# XT60.net
KiCad netlist of a schematic drawn in EAGLE
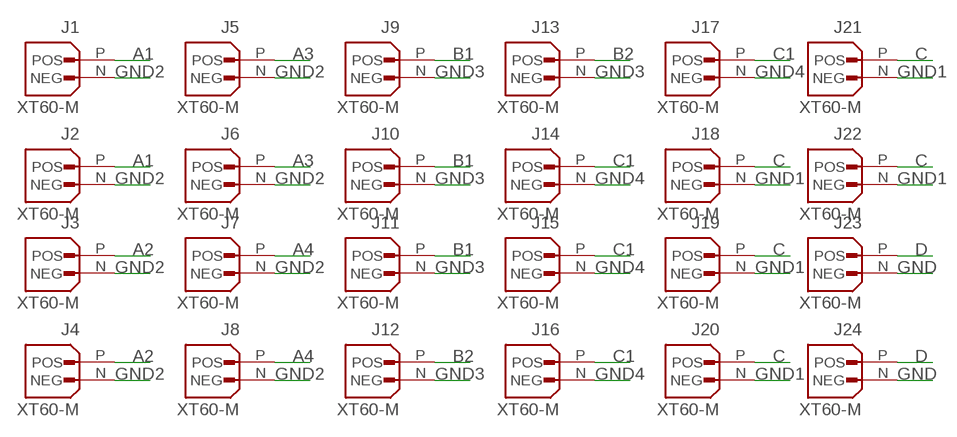
[diagram p0: schematic, sheet 1]

(export (version "E")
  (design (tool "Eeschema 10.0.6"))
  (components
    (comp (ref "J1")
      (value "XT60-M")
      (footprint "eagle-import:AMASS_XT60-M")
      (fields (field (name "MF") "AMASS"))
      (libsource (lib "eagle-import") (part "XT60-M"))
    )
    (comp (ref "J2")
      (value "XT60-M")
      (footprint "eagle-import:AMASS_XT60-M")
      (fields (field (name "MF") "AMASS"))
      (libsource (lib "eagle-import") (part "XT60-M"))
    )
    (comp (ref "J3")
      (value "XT60-M")
      (footprint "eagle-import:AMASS_XT60-M")
      (fields (field (name "MF") "AMASS"))
      (libsource (lib "eagle-import") (part "XT60-M"))
    )
    (comp (ref "J4")
      (value "XT60-M")
      (footprint "eagle-import:AMASS_XT60-M")
      (fields (field (name "MF") "AMASS"))
      (libsource (lib "eagle-import") (part "XT60-M"))
    )
    (comp (ref "J5")
      (value "XT60-M")
      (footprint "eagle-import:AMASS_XT60-M")
      (fields (field (name "MF") "AMASS"))
      (libsource (lib "eagle-import") (part "XT60-M"))
    )
    (comp (ref "J6")
      (value "XT60-M")
      (footprint "eagle-import:AMASS_XT60-M")
      (fields (field (name "MF") "AMASS"))
      (libsource (lib "eagle-import") (part "XT60-M"))
    )
    (comp (ref "J7")
      (value "XT60-M")
      (footprint "eagle-import:AMASS_XT60-M")
      (fields (field (name "MF") "AMASS"))
      (libsource (lib "eagle-import") (part "XT60-M"))
    )
    (comp (ref "J8")
      (value "XT60-M")
      (footprint "eagle-import:AMASS_XT60-M")
      (fields (field (name "MF") "AMASS"))
      (libsource (lib "eagle-import") (part "XT60-M"))
    )
    (comp (ref "J9")
      (value "XT60-M")
      (footprint "eagle-import:AMASS_XT60-M")
      (fields (field (name "MF") "AMASS"))
      (libsource (lib "eagle-import") (part "XT60-M"))
    )
    (comp (ref "J10")
      (value "XT60-M")
      (footprint "eagle-import:AMASS_XT60-M")
      (fields (field (name "MF") "AMASS"))
      (libsource (lib "eagle-import") (part "XT60-M"))
    )
    (comp (ref "J11")
      (value "XT60-M")
      (footprint "eagle-import:AMASS_XT60-M")
      (fields (field (name "MF") "AMASS"))
      (libsource (lib "eagle-import") (part "XT60-M"))
    )
    (comp (ref "J12")
      (value "XT60-M")
      (footprint "eagle-import:AMASS_XT60-M")
      (fields (field (name "MF") "AMASS"))
      (libsource (lib "eagle-import") (part "XT60-M"))
    )
    (comp (ref "J13")
      (value "XT60-M")
      (footprint "eagle-import:AMASS_XT60-M")
      (fields (field (name "MF") "AMASS"))
      (libsource (lib "eagle-import") (part "XT60-M"))
    )
    (comp (ref "J14")
      (value "XT60-M")
      (footprint "eagle-import:AMASS_XT60-M")
      (fields (field (name "MF") "AMASS"))
      (libsource (lib "eagle-import") (part "XT60-M"))
    )
    (comp (ref "J15")
      (value "XT60-M")
      (footprint "eagle-import:AMASS_XT60-M")
      (fields (field (name "MF") "AMASS"))
      (libsource (lib "eagle-import") (part "XT60-M"))
    )
    (comp (ref "J16")
      (value "XT60-M")
      (footprint "eagle-import:AMASS_XT60-M")
      (fields (field (name "MF") "AMASS"))
      (libsource (lib "eagle-import") (part "XT60-M"))
    )
    (comp (ref "J17")
      (value "XT60-M")
      (footprint "eagle-import:AMASS_XT60-M")
      (fields (field (name "MF") "AMASS"))
      (libsource (lib "eagle-import") (part "XT60-M"))
    )
    (comp (ref "J18")
      (value "XT60-M")
      (footprint "eagle-import:AMASS_XT60-M")
      (fields (field (name "MF") "AMASS"))
      (libsource (lib "eagle-import") (part "XT60-M"))
    )
    (comp (ref "J19")
      (value "XT60-M")
      (footprint "eagle-import:AMASS_XT60-M")
      (fields (field (name "MF") "AMASS"))
      (libsource (lib "eagle-import") (part "XT60-M"))
    )
    (comp (ref "J20")
      (value "XT60-M")
      (footprint "eagle-import:AMASS_XT60-M")
      (fields (field (name "MF") "AMASS"))
      (libsource (lib "eagle-import") (part "XT60-M"))
    )
    (comp (ref "J21")
      (value "XT60-M")
      (footprint "eagle-import:AMASS_XT60-M")
      (fields (field (name "MF") "AMASS"))
      (libsource (lib "eagle-import") (part "XT60-M"))
    )
    (comp (ref "J22")
      (value "XT60-M")
      (footprint "eagle-import:AMASS_XT60-M")
      (fields (field (name "MF") "AMASS"))
      (libsource (lib "eagle-import") (part "XT60-M"))
    )
    (comp (ref "J23")
      (value "XT60-M")
      (footprint "eagle-import:AMASS_XT60-M")
      (fields (field (name "MF") "AMASS"))
      (libsource (lib "eagle-import") (part "XT60-M"))
    )
    (comp (ref "J24")
      (value "XT60-M")
      (footprint "eagle-import:AMASS_XT60-M")
      (fields (field (name "MF") "AMASS"))
      (libsource (lib "eagle-import") (part "XT60-M"))
    )
  )
  (nets
    (net (code "1") (name "/A1") (class "Default")
      (node (ref "J1") (pin "P") (pinfunction "POS_P") (pintype "passive"))
      (node (ref "J2") (pin "P") (pinfunction "POS_P") (pintype "passive"))
    )
    (net (code "2") (name "/A2") (class "Default")
      (node (ref "J3") (pin "P") (pinfunction "POS_P") (pintype "passive"))
      (node (ref "J4") (pin "P") (pinfunction "POS_P") (pintype "passive"))
    )
    (net (code "3") (name "/A3") (class "Default")
      (node (ref "J5") (pin "P") (pinfunction "POS_P") (pintype "passive"))
      (node (ref "J6") (pin "P") (pinfunction "POS_P") (pintype "passive"))
    )
    (net (code "4") (name "/A4") (class "Default")
      (node (ref "J7") (pin "P") (pinfunction "POS_P") (pintype "passive"))
      (node (ref "J8") (pin "P") (pinfunction "POS_P") (pintype "passive"))
    )
    (net (code "5") (name "/B1") (class "Default")
      (node (ref "J10") (pin "P") (pinfunction "POS_P") (pintype "passive"))
      (node (ref "J11") (pin "P") (pinfunction "POS_P") (pintype "passive"))
      (node (ref "J9") (pin "P") (pinfunction "POS_P") (pintype "passive"))
    )
    (net (code "6") (name "/B2") (class "Default")
      (node (ref "J12") (pin "P") (pinfunction "POS_P") (pintype "passive"))
      (node (ref "J13") (pin "P") (pinfunction "POS_P") (pintype "passive"))
    )
    (net (code "7") (name "/C") (class "Default")
      (node (ref "J18") (pin "P") (pinfunction "POS_P") (pintype "passive"))
      (node (ref "J19") (pin "P") (pinfunction "POS_P") (pintype "passive"))
      (node (ref "J20") (pin "P") (pinfunction "POS_P") (pintype "passive"))
      (node (ref "J21") (pin "P") (pinfunction "POS_P") (pintype "passive"))
      (node (ref "J22") (pin "P") (pinfunction "POS_P") (pintype "passive"))
    )
    (net (code "8") (name "/C1") (class "Default")
      (node (ref "J14") (pin "P") (pinfunction "POS_P") (pintype "passive"))
      (node (ref "J15") (pin "P") (pinfunction "POS_P") (pintype "passive"))
      (node (ref "J16") (pin "P") (pinfunction "POS_P") (pintype "passive"))
      (node (ref "J17") (pin "P") (pinfunction "POS_P") (pintype "passive"))
    )
    (net (code "9") (name "/D") (class "Default")
      (node (ref "J23") (pin "P") (pinfunction "POS_P") (pintype "passive"))
      (node (ref "J24") (pin "P") (pinfunction "POS_P") (pintype "passive"))
    )
    (net (code "10") (name "/GND") (class "Default")
      (node (ref "J23") (pin "N") (pinfunction "NEG_N") (pintype "passive"))
      (node (ref "J24") (pin "N") (pinfunction "NEG_N") (pintype "passive"))
    )
    (net (code "11") (name "/GND1") (class "Default")
      (node (ref "J18") (pin "N") (pinfunction "NEG_N") (pintype "passive"))
      (node (ref "J19") (pin "N") (pinfunction "NEG_N") (pintype "passive"))
      (node (ref "J20") (pin "N") (pinfunction "NEG_N") (pintype "passive"))
      (node (ref "J21") (pin "N") (pinfunction "NEG_N") (pintype "passive"))
      (node (ref "J22") (pin "N") (pinfunction "NEG_N") (pintype "passive"))
    )
    (net (code "12") (name "/GND2") (class "Default")
      (node (ref "J1") (pin "N") (pinfunction "NEG_N") (pintype "passive"))
      (node (ref "J2") (pin "N") (pinfunction "NEG_N") (pintype "passive"))
      (node (ref "J3") (pin "N") (pinfunction "NEG_N") (pintype "passive"))
      (node (ref "J4") (pin "N") (pinfunction "NEG_N") (pintype "passive"))
      (node (ref "J5") (pin "N") (pinfunction "NEG_N") (pintype "passive"))
      (node (ref "J6") (pin "N") (pinfunction "NEG_N") (pintype "passive"))
      (node (ref "J7") (pin "N") (pinfunction "NEG_N") (pintype "passive"))
      (node (ref "J8") (pin "N") (pinfunction "NEG_N") (pintype "passive"))
    )
    (net (code "13") (name "/GND3") (class "Default")
      (node (ref "J10") (pin "N") (pinfunction "NEG_N") (pintype "passive"))
      (node (ref "J11") (pin "N") (pinfunction "NEG_N") (pintype "passive"))
      (node (ref "J12") (pin "N") (pinfunction "NEG_N") (pintype "passive"))
      (node (ref "J13") (pin "N") (pinfunction "NEG_N") (pintype "passive"))
      (node (ref "J9") (pin "N") (pinfunction "NEG_N") (pintype "passive"))
    )
    (net (code "14") (name "/GND4") (class "Default")
      (node (ref "J14") (pin "N") (pinfunction "NEG_N") (pintype "passive"))
      (node (ref "J15") (pin "N") (pinfunction "NEG_N") (pintype "passive"))
      (node (ref "J16") (pin "N") (pinfunction "NEG_N") (pintype "passive"))
      (node (ref "J17") (pin "N") (pinfunction "NEG_N") (pintype "passive"))
    )
  )
)
